# SimpleCodingBot.net
KiCad netlist of a schematic drawn in EAGLE
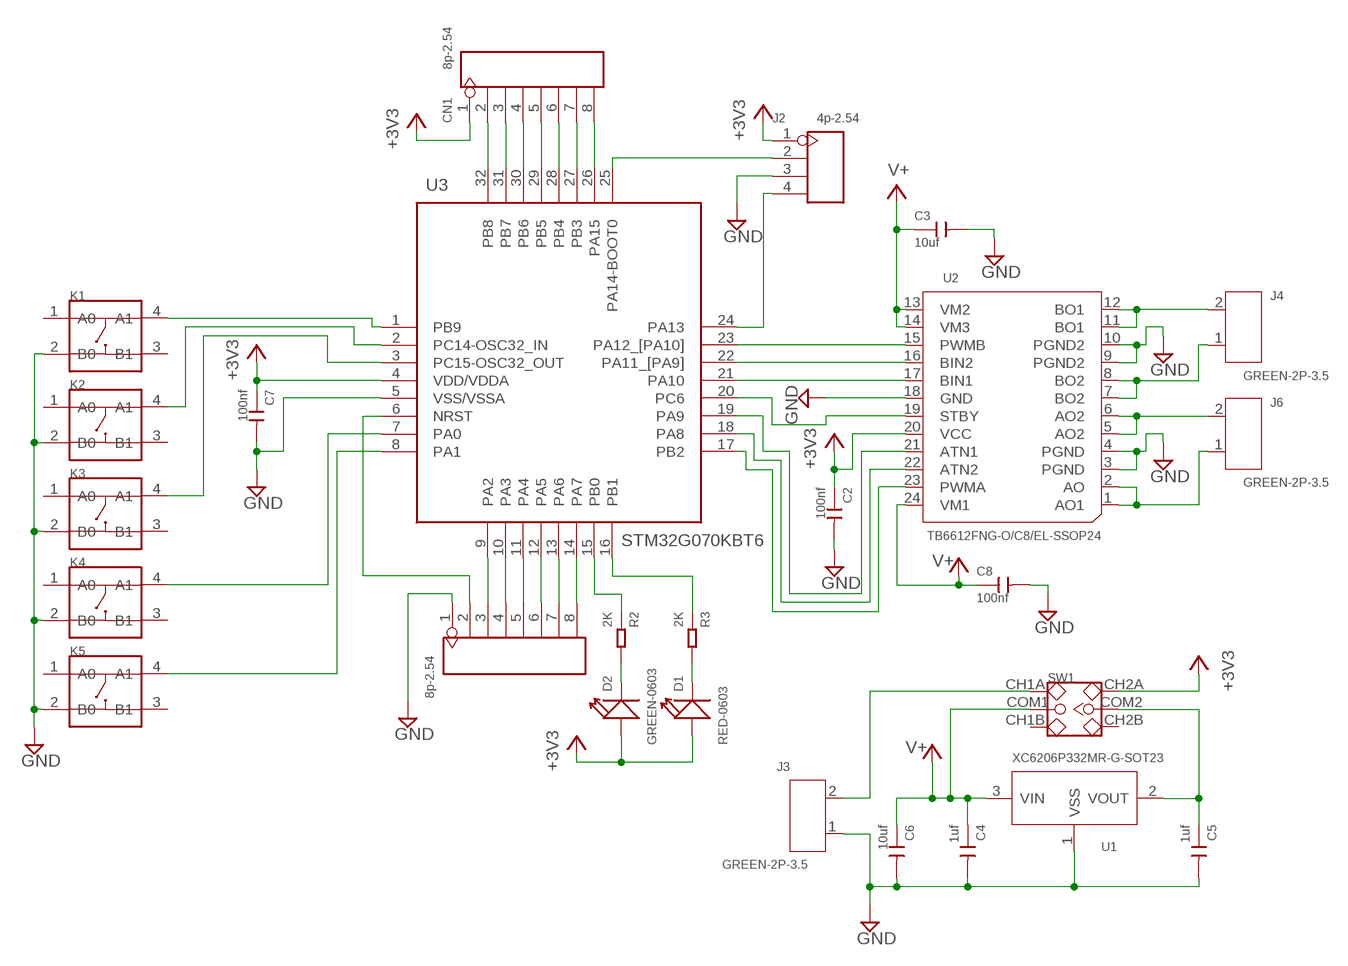
[diagram p0: schematic, sheet 1]

(export (version "E")
  (design (tool "Eeschema 10.0.6"))
  (components
    (comp (ref "C2")
      (value "100nf")
      (footprint "eagle-import:C0603")
      (fields (field (name "MPN") "CC0603KRX7R9BB104"))
      (libsource (lib "eagle-import") (part "CERAMIC-100NF-50V-10%-X7R(0603)"))
    )
    (comp (ref "C3")
      (value "10uf")
      (footprint "eagle-import:C0603")
      (fields (field (name "MPN") "CC0603KRX5R6BB106"))
      (libsource (lib "eagle-import") (part "CERAMIC-10UF-10V-10%-X5R(0603)"))
    )
    (comp (ref "C4")
      (value "1uf")
      (footprint "eagle-import:C0603")
      (fields (field (name "MPN") "CC0603KRX7R8BB105"))
      (libsource (lib "eagle-import") (part "CERAMIC-1UF-25V-10%-X7R(0603)"))
    )
    (comp (ref "C5")
      (value "1uf")
      (footprint "eagle-import:C0603")
      (fields (field (name "MPN") "CC0603KRX7R8BB105"))
      (libsource (lib "eagle-import") (part "CERAMIC-1UF-25V-10%-X7R(0603)"))
    )
    (comp (ref "C6")
      (value "10uf")
      (footprint "eagle-import:C0603")
      (fields (field (name "MPN") "CC0603KRX5R6BB106"))
      (libsource (lib "eagle-import") (part "CERAMIC-10UF-10V-10%-X5R(0603)"))
    )
    (comp (ref "C7")
      (value "100nf")
      (footprint "eagle-import:C0603")
      (fields (field (name "MPN") "CC0603KRX7R9BB104"))
      (libsource (lib "eagle-import") (part "CERAMIC-100NF-50V-10%-X7R(0603)"))
    )
    (comp (ref "C8")
      (value "100nf")
      (footprint "eagle-import:C0603")
      (fields (field (name "MPN") "CC0603KRX7R9BB104"))
      (libsource (lib "eagle-import") (part "CERAMIC-100NF-50V-10%-X7R(0603)"))
    )
    (comp (ref "CN1")
      (value "8p-2.54")
      (footprint "eagle-import:H8-2.54")
      (fields (field (name "MPN") "F185-1108A1BSYC1"))
      (libsource (lib "eagle-import") (part "DIP-BLACK-FEMALE-HEADER-VERT(8P-2.54)"))
    )
    (comp (ref "CN2")
      (value "8p-2.54")
      (footprint "eagle-import:H8-2.54")
      (fields (field (name "MPN") "F185-1108A1BSYC1"))
      (libsource (lib "eagle-import") (part "DIP-BLACK-FEMALE-HEADER-VERT(8P-2.54)"))
    )
    (comp (ref "D1")
      (value "RED-0603")
      (footprint "eagle-import:LED-0603")
      (fields (field (name "MPN") "19-217-R6C-AL1M2VY-3T"))
      (libsource (lib "eagle-import") (part "LED-SMD-RED-DIFFUSED(0603)"))
    )
    (comp (ref "D2")
      (value "GREEN-0603")
      (footprint "eagle-import:LED-0603")
      (fields (field (name "MPN") "19-217-G7C-AN1P2-3T"))
      (libsource (lib "eagle-import") (part "SMD-LED-CLEAR-GREEN(0603)"))
    )
    (comp (ref "J2")
      (value "4p-2.54")
      (footprint "eagle-import:H4-2.54")
      (fields (field (name "MPN") "P125-1104A0BS116A1"))
      (libsource (lib "eagle-import") (part "DIP-BLACK-MALE-HEADER-VERT(4P-2.54)"))
    )
    (comp (ref "J3")
      (value "GREEN-2P-3.5")
      (footprint "eagle-import:H2-3.5-7.0X7.0MM")
      (libsource (lib "eagle-import") (part "SCREW-TERMINAL-GREEN(2P-3.5)"))
    )
    (comp (ref "J4")
      (value "GREEN-2P-3.5")
      (footprint "eagle-import:H2-3.5-7.0X7.0MM")
      (libsource (lib "eagle-import") (part "SCREW-TERMINAL-GREEN(2P-3.5)"))
    )
    (comp (ref "J6")
      (value "GREEN-2P-3.5")
      (footprint "eagle-import:H2-3.5-7.0X7.0MM")
      (libsource (lib "eagle-import") (part "SCREW-TERMINAL-GREEN(2P-3.5)"))
    )
    (comp (ref "K1")
      (value "DIP-SWITCH-TACTILE-SPST-NO/TS-1109(4P-D6.0MM)'TS-1109'")
      (footprint "eagle-import:SW4-6.0X6.0X5.0MM")
      (libsource (lib "eagle-import") (part "DIP-SWITCH-TACTILE-SPST-NO/TS-1109(4P-D6.0MM)'TS-1109'"))
    )
    (comp (ref "K2")
      (value "DIP-SWITCH-TACTILE-SPST-NO/TS-1109(4P-D6.0MM)'TS-1109'")
      (footprint "eagle-import:SW4-6.0X6.0X5.0MM")
      (libsource (lib "eagle-import") (part "DIP-SWITCH-TACTILE-SPST-NO/TS-1109(4P-D6.0MM)'TS-1109'"))
    )
    (comp (ref "K3")
      (value "DIP-SWITCH-TACTILE-SPST-NO/TS-1109(4P-D6.0MM)'TS-1109'")
      (footprint "eagle-import:SW4-6.0X6.0X5.0MM")
      (libsource (lib "eagle-import") (part "DIP-SWITCH-TACTILE-SPST-NO/TS-1109(4P-D6.0MM)'TS-1109'"))
    )
    (comp (ref "K4")
      (value "DIP-SWITCH-TACTILE-SPST-NO/TS-1109(4P-D6.0MM)'TS-1109'")
      (footprint "eagle-import:SW4-6.0X6.0X5.0MM")
      (libsource (lib "eagle-import") (part "DIP-SWITCH-TACTILE-SPST-NO/TS-1109(4P-D6.0MM)'TS-1109'"))
    )
    (comp (ref "K5")
      (value "DIP-SWITCH-TACTILE-SPST-NO/TS-1109(4P-D6.0MM)'TS-1109'")
      (footprint "eagle-import:SW4-6.0X6.0X5.0MM")
      (libsource (lib "eagle-import") (part "DIP-SWITCH-TACTILE-SPST-NO/TS-1109(4P-D6.0MM)'TS-1109'"))
    )
    (comp (ref "R2")
      (value "2K")
      (footprint "eagle-import:R0603")
      (fields (field (name "MPN") "RC0603FR-072KL"))
      (libsource (lib "eagle-import") (part "SMD-RES-2K-1%-1/10W(0603)"))
    )
    (comp (ref "R3")
      (value "2K")
      (footprint "eagle-import:R0603")
      (fields (field (name "MPN") "RC0603FR-072KL"))
      (libsource (lib "eagle-import") (part "SMD-RES-2K-1%-1/10W(0603)"))
    )
    (comp (ref "SW1")
      (value "DIP-TOGGLE-SWITCH-2CH-(2X3P-2.54)")
      (footprint "eagle-import:SW6-2.54-9.0X3.5X3.2+2.0MM")
      (fields (field (name "MPN") "MS-22D18 G2 ROHS"))
      (libsource (lib "eagle-import") (part "DIP-TOGGLE-SWITCH-2CH-(2X3P-2.54)"))
    )
    (comp (ref "U1")
      (value "XC6206P332MR-G-SOT23")
      (footprint "eagle-import:SOT-23")
      (fields (field (name "MPN") "XC6206P332MR-G"))
      (libsource (lib "eagle-import") (part "PMIC-LDO-XC6206P332MR-G(SOT23)"))
    )
    (comp (ref "U2")
      (value "TB6612FNG-O/C8/EL-SSOP24")
      (footprint "eagle-import:SSOP24-0.65-8.9X5.3MM")
      (fields (field (name "MPN") "TB6612FNG-O/C8/EL"))
      (libsource (lib "eagle-import") (part "DRIVER-TB6612FNG-O/C8/EL(SSOP24)"))
    )
    (comp (ref "U3")
      (value "STM32G070KBT6")
      (footprint "eagle-import:QFP80P900X900X160-32N")
      (fields (field (name "MOUSER_PART_NUMBER") "511-STM32G070KBT6"))
      (libsource (lib "eagle-import") (part "STM32G070KBT6"))
    )
  )
  (nets
    (net (code "1") (name "+3V3") (class "Default")
      (node (ref "C2") (pin "1") (pinfunction "1_1") (pintype "passive"))
      (node (ref "C7") (pin "1") (pinfunction "1_1") (pintype "passive"))
      (node (ref "CN1") (pin "1") (pinfunction "1_1") (pintype "bidirectional"))
      (node (ref "D1") (pin "+") (pinfunction "+_+") (pintype "passive"))
      (node (ref "D2") (pin "+") (pinfunction "+_+") (pintype "passive"))
      (node (ref "J2") (pin "1") (pinfunction "P$1_1") (pintype "bidirectional"))
      (node (ref "SW1") (pin "CH2A") (pinfunction "CH2A_CH2A") (pintype "bidirectional"))
      (node (ref "U2") (pin "20") (pinfunction "VCC_20") (pintype "bidirectional"))
      (node (ref "U3") (pin "4") (pinfunction "VDD/VDDA_4") (pintype "power_in"))
    )
    (net (code "2") (name "GND") (class "Default")
      (node (ref "C2") (pin "2") (pinfunction "2_2") (pintype "passive"))
      (node (ref "C3") (pin "2") (pinfunction "2_2") (pintype "passive"))
      (node (ref "C4") (pin "2") (pinfunction "2_2") (pintype "passive"))
      (node (ref "C5") (pin "2") (pinfunction "2_2") (pintype "passive"))
      (node (ref "C6") (pin "2") (pinfunction "2_2") (pintype "passive"))
      (node (ref "C7") (pin "2") (pinfunction "2_2") (pintype "passive"))
      (node (ref "C8") (pin "2") (pinfunction "2_2") (pintype "passive"))
      (node (ref "CN2") (pin "1") (pinfunction "1_1") (pintype "bidirectional"))
      (node (ref "J2") (pin "3") (pinfunction "P$3_3") (pintype "bidirectional"))
      (node (ref "J3") (pin "1") (pinfunction "1_1") (pintype "bidirectional"))
      (node (ref "K1") (pin "2") (pinfunction "B0_2") (pintype "bidirectional"))
      (node (ref "K2") (pin "2") (pinfunction "B0_2") (pintype "bidirectional"))
      (node (ref "K3") (pin "2") (pinfunction "B0_2") (pintype "bidirectional"))
      (node (ref "K4") (pin "2") (pinfunction "B0_2") (pintype "bidirectional"))
      (node (ref "K5") (pin "2") (pinfunction "B0_2") (pintype "bidirectional"))
      (node (ref "U1") (pin "1") (pinfunction "VSS_1") (pintype "power_in"))
      (node (ref "U2") (pin "10") (pinfunction "PGND2_10") (pintype "bidirectional"))
      (node (ref "U2") (pin "18") (pinfunction "GND_18") (pintype "bidirectional"))
      (node (ref "U2") (pin "3") (pinfunction "PGND_3") (pintype "bidirectional"))
      (node (ref "U2") (pin "4") (pinfunction "PGND_4") (pintype "bidirectional"))
      (node (ref "U2") (pin "9") (pinfunction "PGND2_9") (pintype "bidirectional"))
      (node (ref "U3") (pin "5") (pinfunction "VSS/VSSA_5") (pintype "power_in"))
    )
    (net (code "3") (name "Net-(D1-Pad-)") (class "Default")
      (node (ref "D1") (pin "-") (pinfunction "-_-") (pintype "passive"))
      (node (ref "R3") (pin "2") (pinfunction "2_2") (pintype "passive"))
    )
    (net (code "4") (name "Net-(D2-Pad-)") (class "Default")
      (node (ref "D2") (pin "-") (pinfunction "-_-") (pintype "passive"))
      (node (ref "R2") (pin "2") (pinfunction "2_2") (pintype "passive"))
    )
    (net (code "5") (name "Net-(J2-P$2)") (class "Default")
      (node (ref "J2") (pin "2") (pinfunction "P$2_2") (pintype "bidirectional"))
      (node (ref "U3") (pin "25") (pinfunction "PA14-BOOT0_25") (pintype "bidirectional"))
    )
    (net (code "6") (name "Net-(J2-P$4)") (class "Default")
      (node (ref "J2") (pin "4") (pinfunction "P$4_4") (pintype "bidirectional"))
      (node (ref "U3") (pin "24") (pinfunction "PA13_24") (pintype "bidirectional"))
    )
    (net (code "7") (name "Net-(J3-Pad2)") (class "Default")
      (node (ref "J3") (pin "2") (pinfunction "2_2") (pintype "bidirectional"))
      (node (ref "SW1") (pin "CH1A") (pinfunction "CH1A_CH1A") (pintype "bidirectional"))
    )
    (net (code "8") (name "Net-(J4-Pad1)") (class "Default")
      (node (ref "J4") (pin "1") (pinfunction "1_1") (pintype "bidirectional"))
      (node (ref "U2") (pin "7") (pinfunction "BO2_7") (pintype "bidirectional"))
      (node (ref "U2") (pin "8") (pinfunction "BO2_8") (pintype "bidirectional"))
    )
    (net (code "9") (name "Net-(J4-Pad2)") (class "Default")
      (node (ref "J4") (pin "2") (pinfunction "2_2") (pintype "bidirectional"))
      (node (ref "U2") (pin "11") (pinfunction "BO1_11") (pintype "bidirectional"))
      (node (ref "U2") (pin "12") (pinfunction "BO1_12") (pintype "bidirectional"))
    )
    (net (code "10") (name "Net-(J6-Pad2)") (class "Default")
      (node (ref "J6") (pin "2") (pinfunction "2_2") (pintype "bidirectional"))
      (node (ref "U2") (pin "5") (pinfunction "AO2_5") (pintype "bidirectional"))
      (node (ref "U2") (pin "6") (pinfunction "AO2_6") (pintype "bidirectional"))
    )
    (net (code "11") (name "Net-(K1-A1)") (class "Default")
      (node (ref "K1") (pin "4") (pinfunction "A1_4") (pintype "bidirectional"))
      (node (ref "U3") (pin "1") (pinfunction "PB9_1") (pintype "bidirectional"))
    )
    (net (code "12") (name "Net-(K2-A1)") (class "Default")
      (node (ref "K2") (pin "4") (pinfunction "A1_4") (pintype "bidirectional"))
      (node (ref "U3") (pin "2") (pinfunction "PC14-OSC32_IN_2") (pintype "bidirectional"))
    )
    (net (code "13") (name "Net-(K3-A1)") (class "Default")
      (node (ref "K3") (pin "4") (pinfunction "A1_4") (pintype "bidirectional"))
      (node (ref "U3") (pin "3") (pinfunction "PC15-OSC32_OUT_3") (pintype "bidirectional"))
    )
    (net (code "14") (name "Net-(K4-A1)") (class "Default")
      (node (ref "K4") (pin "4") (pinfunction "A1_4") (pintype "bidirectional"))
      (node (ref "U3") (pin "7") (pinfunction "PA0_7") (pintype "bidirectional"))
    )
    (net (code "15") (name "Net-(K5-A1)") (class "Default")
      (node (ref "K5") (pin "4") (pinfunction "A1_4") (pintype "bidirectional"))
      (node (ref "U3") (pin "8") (pinfunction "PA1_8") (pintype "bidirectional"))
    )
    (net (code "16") (name "Net-(U1-VOUT)") (class "Default")
      (node (ref "C5") (pin "1") (pinfunction "1_1") (pintype "passive"))
      (node (ref "SW1") (pin "COM2") (pinfunction "COM2_COM2") (pintype "bidirectional"))
      (node (ref "U1") (pin "2") (pinfunction "VOUT_2") (pintype "output"))
    )
    (net (code "17") (name "Net-(U2-AO)") (class "Default")
      (node (ref "J6") (pin "1") (pinfunction "1_1") (pintype "bidirectional"))
      (node (ref "U2") (pin "1") (pinfunction "AO1_1") (pintype "bidirectional"))
      (node (ref "U2") (pin "2") (pinfunction "AO_2") (pintype "bidirectional"))
    )
    (net (code "18") (name "Net-(U2-ATN1)") (class "Default")
      (node (ref "U2") (pin "21") (pinfunction "ATN1_21") (pintype "bidirectional"))
      (node (ref "U3") (pin "19") (pinfunction "PA9_19") (pintype "bidirectional"))
    )
    (net (code "19") (name "Net-(U2-ATN2)") (class "Default")
      (node (ref "U2") (pin "22") (pinfunction "ATN2_22") (pintype "bidirectional"))
      (node (ref "U3") (pin "18") (pinfunction "PA8_18") (pintype "bidirectional"))
    )
    (net (code "20") (name "Net-(U2-BIN1)") (class "Default")
      (node (ref "U2") (pin "17") (pinfunction "BIN1_17") (pintype "bidirectional"))
      (node (ref "U3") (pin "21") (pinfunction "PA10_21") (pintype "bidirectional"))
    )
    (net (code "21") (name "Net-(U2-BIN2)") (class "Default")
      (node (ref "U2") (pin "16") (pinfunction "BIN2_16") (pintype "bidirectional"))
      (node (ref "U3") (pin "22") (pinfunction "PA11_[PA9]_22") (pintype "bidirectional"))
    )
    (net (code "22") (name "Net-(U2-PWMA)") (class "Default")
      (node (ref "U2") (pin "23") (pinfunction "PWMA_23") (pintype "bidirectional"))
      (node (ref "U3") (pin "17") (pinfunction "PB2_17") (pintype "bidirectional"))
    )
    (net (code "23") (name "Net-(U2-PWMB)") (class "Default")
      (node (ref "U2") (pin "15") (pinfunction "PWMB_15") (pintype "bidirectional"))
      (node (ref "U3") (pin "23") (pinfunction "PA12_[PA10]_23") (pintype "bidirectional"))
    )
    (net (code "24") (name "Net-(U2-STBY)") (class "Default")
      (node (ref "U2") (pin "19") (pinfunction "STBY_19") (pintype "bidirectional"))
      (node (ref "U3") (pin "20") (pinfunction "PC6_20") (pintype "bidirectional"))
    )
    (net (code "25") (name "Net-(U3-NRST)") (class "Default")
      (node (ref "CN2") (pin "2") (pinfunction "2_2") (pintype "bidirectional"))
      (node (ref "U3") (pin "6") (pinfunction "NRST_6") (pintype "bidirectional"))
    )
    (net (code "26") (name "Net-(U3-PA2)") (class "Default")
      (node (ref "CN2") (pin "3") (pinfunction "3_3") (pintype "bidirectional"))
      (node (ref "U3") (pin "9") (pinfunction "PA2_9") (pintype "bidirectional"))
    )
    (net (code "27") (name "Net-(U3-PA3)") (class "Default")
      (node (ref "CN2") (pin "4") (pinfunction "4_4") (pintype "bidirectional"))
      (node (ref "U3") (pin "10") (pinfunction "PA3_10") (pintype "bidirectional"))
    )
    (net (code "28") (name "Net-(U3-PA4)") (class "Default")
      (node (ref "CN2") (pin "5") (pinfunction "5_5") (pintype "bidirectional"))
      (node (ref "U3") (pin "11") (pinfunction "PA4_11") (pintype "bidirectional"))
    )
    (net (code "29") (name "Net-(U3-PA5)") (class "Default")
      (node (ref "CN2") (pin "6") (pinfunction "6_6") (pintype "bidirectional"))
      (node (ref "U3") (pin "12") (pinfunction "PA5_12") (pintype "bidirectional"))
    )
    (net (code "30") (name "Net-(U3-PA6)") (class "Default")
      (node (ref "CN2") (pin "7") (pinfunction "7_7") (pintype "bidirectional"))
      (node (ref "U3") (pin "13") (pinfunction "PA6_13") (pintype "bidirectional"))
    )
    (net (code "31") (name "Net-(U3-PA7)") (class "Default")
      (node (ref "CN2") (pin "8") (pinfunction "8_8") (pintype "bidirectional"))
      (node (ref "U3") (pin "14") (pinfunction "PA7_14") (pintype "bidirectional"))
    )
    (net (code "32") (name "Net-(U3-PA15)") (class "Default")
      (node (ref "CN1") (pin "8") (pinfunction "8_8") (pintype "bidirectional"))
      (node (ref "U3") (pin "26") (pinfunction "PA15_26") (pintype "bidirectional"))
    )
    (net (code "33") (name "Net-(U3-PB0)") (class "Default")
      (node (ref "R2") (pin "1") (pinfunction "1_1") (pintype "passive"))
      (node (ref "U3") (pin "15") (pinfunction "PB0_15") (pintype "bidirectional"))
    )
    (net (code "34") (name "Net-(U3-PB1)") (class "Default")
      (node (ref "R3") (pin "1") (pinfunction "1_1") (pintype "passive"))
      (node (ref "U3") (pin "16") (pinfunction "PB1_16") (pintype "bidirectional"))
    )
    (net (code "35") (name "Net-(U3-PB3)") (class "Default")
      (node (ref "CN1") (pin "7") (pinfunction "7_7") (pintype "bidirectional"))
      (node (ref "U3") (pin "27") (pinfunction "PB3_27") (pintype "bidirectional"))
    )
    (net (code "36") (name "Net-(U3-PB4)") (class "Default")
      (node (ref "CN1") (pin "6") (pinfunction "6_6") (pintype "bidirectional"))
      (node (ref "U3") (pin "28") (pinfunction "PB4_28") (pintype "bidirectional"))
    )
    (net (code "37") (name "Net-(U3-PB5)") (class "Default")
      (node (ref "CN1") (pin "5") (pinfunction "5_5") (pintype "bidirectional"))
      (node (ref "U3") (pin "29") (pinfunction "PB5_29") (pintype "bidirectional"))
    )
    (net (code "38") (name "Net-(U3-PB6)") (class "Default")
      (node (ref "CN1") (pin "4") (pinfunction "4_4") (pintype "bidirectional"))
      (node (ref "U3") (pin "30") (pinfunction "PB6_30") (pintype "bidirectional"))
    )
    (net (code "39") (name "Net-(U3-PB7)") (class "Default")
      (node (ref "CN1") (pin "3") (pinfunction "3_3") (pintype "bidirectional"))
      (node (ref "U3") (pin "31") (pinfunction "PB7_31") (pintype "bidirectional"))
    )
    (net (code "40") (name "Net-(U3-PB8)") (class "Default")
      (node (ref "CN1") (pin "2") (pinfunction "2_2") (pintype "bidirectional"))
      (node (ref "U3") (pin "32") (pinfunction "PB8_32") (pintype "bidirectional"))
    )
    (net (code "41") (name "V+") (class "Default")
      (node (ref "C3") (pin "1") (pinfunction "1_1") (pintype "passive"))
      (node (ref "C4") (pin "1") (pinfunction "1_1") (pintype "passive"))
      (node (ref "C6") (pin "1") (pinfunction "1_1") (pintype "passive"))
      (node (ref "C8") (pin "1") (pinfunction "1_1") (pintype "passive"))
      (node (ref "SW1") (pin "COM1") (pinfunction "COM1_COM1") (pintype "bidirectional"))
      (node (ref "U1") (pin "3") (pinfunction "VIN_3") (pintype "input"))
      (node (ref "U2") (pin "13") (pinfunction "VM2_13") (pintype "bidirectional"))
      (node (ref "U2") (pin "14") (pinfunction "VM3_14") (pintype "bidirectional"))
      (node (ref "U2") (pin "24") (pinfunction "VM1_24") (pintype "bidirectional"))
    )
    (net (code "42") (name "unconnected-(K1-A0-Pad1)") (class "Default")
      (node (ref "K1") (pin "1") (pinfunction "A0_1") (pintype "bidirectional"))
    )
    (net (code "43") (name "unconnected-(K1-B1-Pad3)") (class "Default")
      (node (ref "K1") (pin "3") (pinfunction "B1_3") (pintype "bidirectional"))
    )
    (net (code "44") (name "unconnected-(K2-A0-Pad1)") (class "Default")
      (node (ref "K2") (pin "1") (pinfunction "A0_1") (pintype "bidirectional"))
    )
    (net (code "45") (name "unconnected-(K2-B1-Pad3)") (class "Default")
      (node (ref "K2") (pin "3") (pinfunction "B1_3") (pintype "bidirectional"))
    )
    (net (code "46") (name "unconnected-(K3-A0-Pad1)") (class "Default")
      (node (ref "K3") (pin "1") (pinfunction "A0_1") (pintype "bidirectional"))
    )
    (net (code "47") (name "unconnected-(K3-B1-Pad3)") (class "Default")
      (node (ref "K3") (pin "3") (pinfunction "B1_3") (pintype "bidirectional"))
    )
    (net (code "48") (name "unconnected-(K4-A0-Pad1)") (class "Default")
      (node (ref "K4") (pin "1") (pinfunction "A0_1") (pintype "bidirectional"))
    )
    (net (code "49") (name "unconnected-(K4-B1-Pad3)") (class "Default")
      (node (ref "K4") (pin "3") (pinfunction "B1_3") (pintype "bidirectional"))
    )
    (net (code "50") (name "unconnected-(K5-A0-Pad1)") (class "Default")
      (node (ref "K5") (pin "1") (pinfunction "A0_1") (pintype "bidirectional"))
    )
    (net (code "51") (name "unconnected-(K5-B1-Pad3)") (class "Default")
      (node (ref "K5") (pin "3") (pinfunction "B1_3") (pintype "bidirectional"))
    )
    (net (code "52") (name "unconnected-(SW1-PadCH1B)") (class "Default")
      (node (ref "SW1") (pin "CH1B") (pinfunction "CH1B_CH1B") (pintype "bidirectional"))
    )
    (net (code "53") (name "unconnected-(SW1-PadCH2B)") (class "Default")
      (node (ref "SW1") (pin "CH2B") (pinfunction "CH2B_CH2B") (pintype "bidirectional"))
    )
  )
)
